# MCLR_PIC.net
KiCad netlist of a schematic drawn in Altium Designer
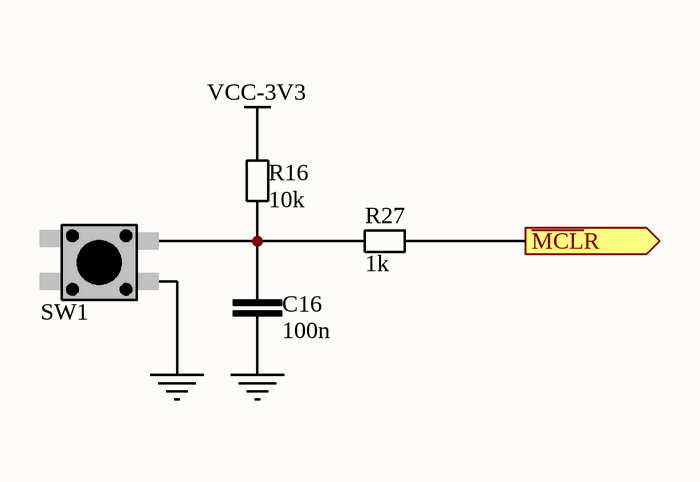
[diagram p0: MCLR_PIC.SchDoc]

(export (version "E")
  (design (tool "Eeschema 10.0.6"))
  (components
    (comp (ref "C16")
      (value "100n")
      (footprint "CER_0603")
      (description "CAP CER 100n 10V X5R 10% 0603")
      (libsource (lib "Capacitors") (part "06032105"))
    )
    (comp (ref "R16")
      (value "10k")
      (footprint "RESC2013X38N-0805-NOOVERLAY")
      (description "RES SMD 10 kOhm 1/8W 0805")
      (libsource (lib "Resistors") (part "000001002"))
    )
    (comp (ref "R27")
      (value "1k")
      (footprint "RESC2013X38N-0805-NOOVERLAY")
      (description "RES SMD 1 kOhm 1/8W 0805")
      (fields (field (name "POWER") "0.125W, 1/8W"))
      (libsource (lib "Resistors") (part "00001001"))
    )
    (comp (ref "SW1")
      (value "TASTER")
      (footprint "TASTER_SMD")
      (libsource (lib "Electro_Mechanical") (part "TASTER"))
    )
  )
  (nets
    (net (code "1") (name "/~{MCL}R") (class "Default")
      (node (ref "R27") (pin "2") (pinfunction "2_2") (pintype "passive"))
    )
    (net (code "2") (name "GND") (class "Default")
      (node (ref "C16") (pin "1") (pinfunction "1_1") (pintype "passive"))
      (node (ref "SW1") (pin "1") (pinfunction "1_1") (pintype "passive"))
    )
    (net (code "3") (name "Net-(C16-Pad2)") (class "Default")
      (node (ref "C16") (pin "2") (pinfunction "2_2") (pintype "passive"))
      (node (ref "R16") (pin "1") (pinfunction "1_1") (pintype "passive"))
      (node (ref "R27") (pin "1") (pinfunction "1_1") (pintype "passive"))
      (node (ref "SW1") (pin "2") (pinfunction "2_2") (pintype "passive"))
    )
    (net (code "4") (name "VCC-3V3") (class "Default")
      (node (ref "R16") (pin "2") (pinfunction "2_2") (pintype "passive"))
    )
  )
)
